# DD2088PoE_Daisy_Chain_IMU.net
KiCad netlist of a schematic drawn in Altium Designer
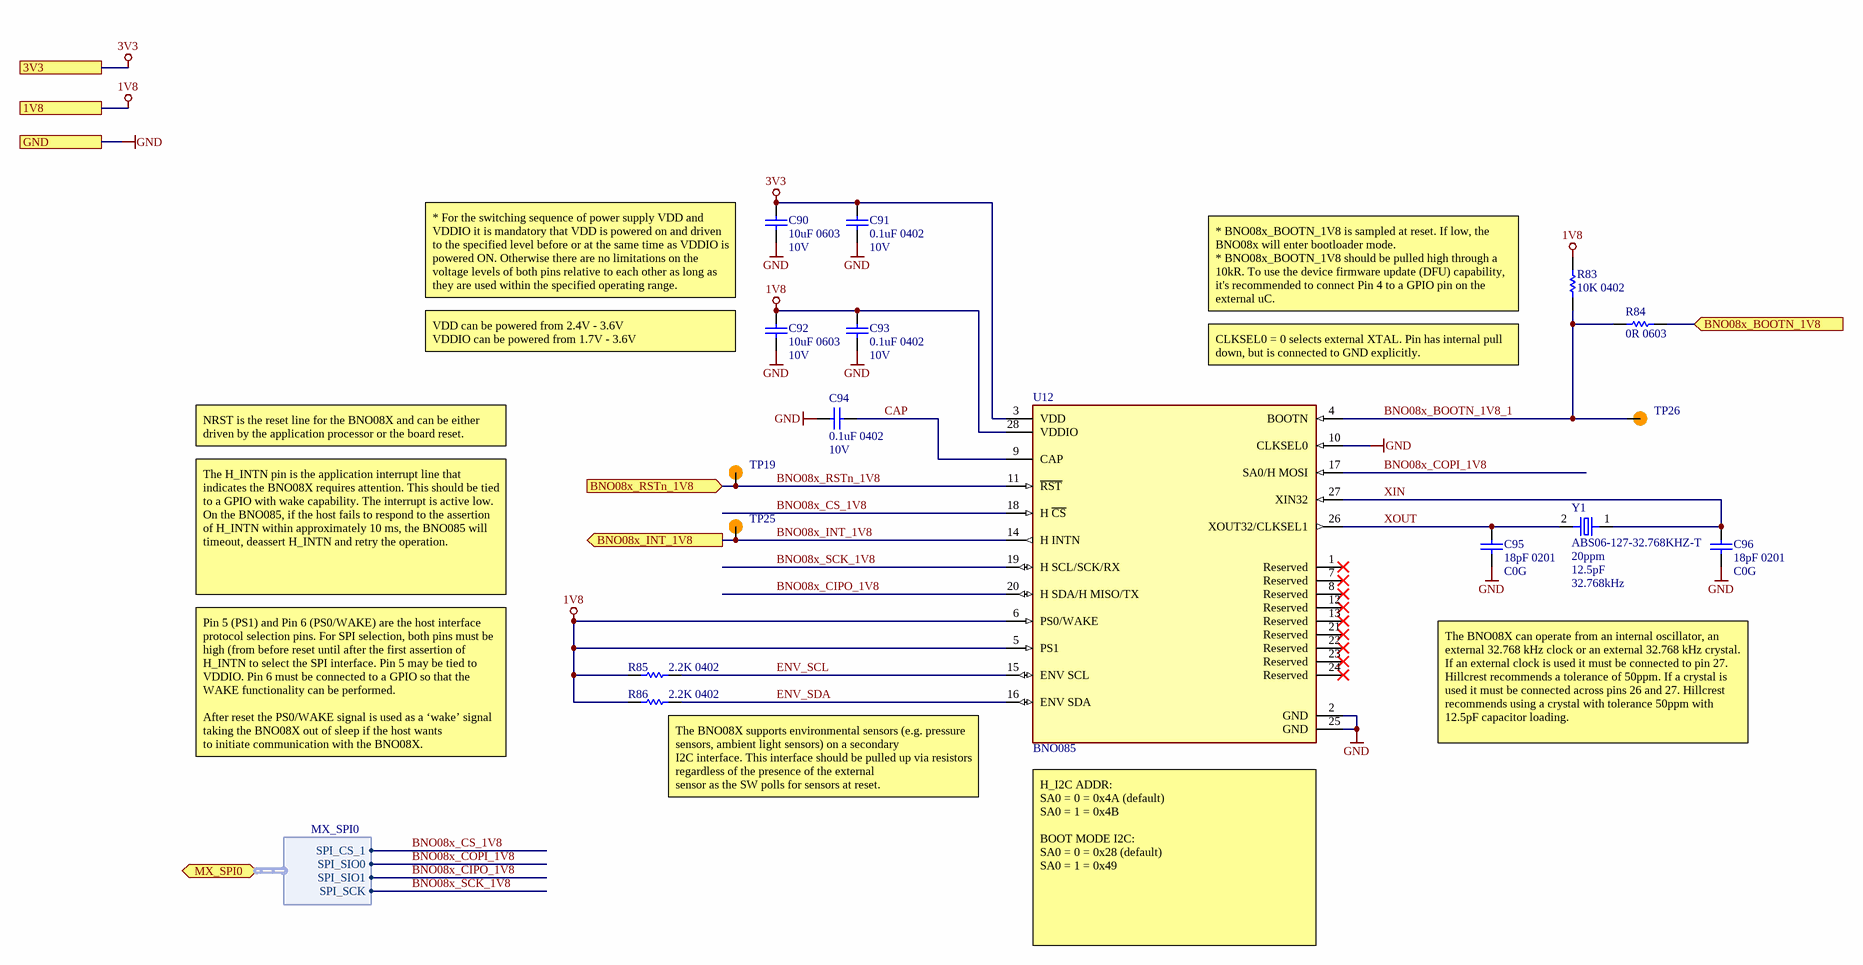
[diagram p0: DD2088PoE_Daisy_Chain_IMU.SchDoc]

(export (version "E")
  (design (tool "Eeschema 10.0.6"))
  (components
    (comp (ref "C90")
      (value "10uF 0603")
      (footprint "CAP_Altium_Vault_Generic:CAPC0603(1608)100_L")
      (description "CAP CER 10UF 10V X5R 0603 20%")
      (fields (field (name "TOLERANCE") "20%") (field (name "VOLTAGE RATING") "10V"))
      (libsource (lib "LuxonisMaster") (part "GRM188R61A106ME69D"))
    )
    (comp (ref "C91")
      (value "0.1uF 0402")
      (footprint "CAP_Altium_Vault_Generic:CAPC0402(1005)70_L")
      (description "CAP CER 0.1UF 10V X7R 0402 5%")
      (fields (field (name "TOLERANCE") "5%") (field (name "VOLTAGE RATING") "10V"))
      (libsource (lib "LuxonisMaster") (part "GRM155R71A104JA01D"))
    )
    (comp (ref "C92")
      (value "10uF 0603")
      (footprint "CAP_Altium_Vault_Generic:CAPC0603(1608)100_L")
      (description "CAP CER 10UF 10V X5R 0603 20%")
      (fields (field (name "TOLERANCE") "20%") (field (name "VOLTAGE RATING") "10V"))
      (libsource (lib "LuxonisMaster") (part "GRM188R61A106ME69D"))
    )
    (comp (ref "C93")
      (value "0.1uF 0402")
      (footprint "CAP_Altium_Vault_Generic:CAPC0402(1005)70_L")
      (description "CAP CER 0.1UF 10V X7R 0402 5%")
      (fields (field (name "TOLERANCE") "5%") (field (name "VOLTAGE RATING") "10V"))
      (libsource (lib "LuxonisMaster") (part "GRM155R71A104JA01D"))
    )
    (comp (ref "C94")
      (value "0.1uF 0402")
      (footprint "CAP_Altium_Vault_Generic:CAPC0402(1005)70_L")
      (description "CAP CER 0.1UF 10V X7R 0402 5%")
      (fields (field (name "TOLERANCE") "5%") (field (name "VOLTAGE RATING") "10V"))
      (libsource (lib "LuxonisMaster") (part "GRM155R71A104JA01D"))
    )
    (comp (ref "C95")
      (value "18pF 0201")
      (footprint "CAP_Altium_Vault_Generic:CAPC0201(0603)33_L")
      (description "Cap Ceramic 18pF 25V C0G 1% Pad SMD 0201 125C T/R")
      (fields (field (name "TOLERANCE") "1%") (field (name "DIELECTRIC") "C0G"))
      (libsource (lib "BW1092_R0M0E0") (part "GRM0335C1E180FA01D"))
    )
    (comp (ref "C96")
      (value "18pF 0201")
      (footprint "CAP_Altium_Vault_Generic:CAPC0201(0603)33_L")
      (description "Cap Ceramic 18pF 25V C0G 1% Pad SMD 0201 125C T/R")
      (fields (field (name "TOLERANCE") "1%") (field (name "DIELECTRIC") "C0G"))
      (libsource (lib "BW1092_R0M0E0") (part "GRM0335C1E180FA01D"))
    )
    (comp (ref "R83")
      (value "10K 0402")
      (footprint "RES_Altium_Vault_Generic:RESC0402(1005)_L")
      (fields (field (name "TOLERANCE") "1%"))
      (libsource (lib "LuxonisMaster") (part "RC0402FR-1310KL"))
    )
    (comp (ref "R84")
      (value "0R 0603")
      (footprint "RES_Altium_Vault_Generic:RESC0603(1608)_L")
      (fields (field (name "TOLERANCE") "5%"))
      (libsource (lib "LuxonisMaster") (part "CRCW06030000Z0EA"))
    )
    (comp (ref "R85")
      (value "2.2K 0402")
      (footprint "RES_Altium_Vault_Generic:RESC0402(1005)_L")
      (description "RES SMD 2.2K OHM 1% 1/16W 0402")
      (fields (field (name "TOLERANCE") "1%"))
      (libsource (lib "LuxonisMaster") (part "RC0402FR-072K2L"))
    )
    (comp (ref "R86")
      (value "2.2K 0402")
      (footprint "RES_Altium_Vault_Generic:RESC0402(1005)_L")
      (description "RES SMD 2.2K OHM 1% 1/16W 0402")
      (fields (field (name "TOLERANCE") "1%"))
      (libsource (lib "LuxonisMaster") (part "RC0402FR-072K2L"))
    )
    (comp (ref "TP19")
      (value "TP100_200_NS")
      (footprint "TP100_200_NS")
      (libsource (lib "LuxonisMaster") (part "TEST_POINT"))
    )
    (comp (ref "TP25")
      (value "TP100_200_NS")
      (footprint "TP100_200_NS")
      (libsource (lib "LuxonisMaster") (part "TEST_POINT"))
    )
    (comp (ref "TP26")
      (value "TP100_200_NS")
      (footprint "TP100_200_NS")
      (libsource (lib "LuxonisMaster") (part "TEST_POINT"))
    )
    (comp (ref "U12")
      (value "BNO085")
      (footprint "BW1092_R0M0E0:BNO085")
      (description "IMU ACCEL/GYRO/MAG I2C 32BIT")
      (libsource (lib "BW1092_R0M0E0") (part "BNO085"))
    )
    (comp (ref "Y1")
      (value "ABS06-127-32.768KHZ-T")
      (footprint "BW1092_R0M0E0:ABS06-127-32.768KHZ-T")
      (description "CRYSTAL 32.768kHz ±20ppm Crystal 12.5pF 90 kOhms 2-SMD, No Lead")
      (fields
        (field (name "FREQUENCY TOLERANCE") "20ppm")
        (field (name "LOAD CAPACITANCE") "12.5pF")
        (field (name "FREQUENCY") "32.768kHz")
      )
      (libsource (lib "BW1092_R0M0E0") (part "ABS06-127-32.768KHZ-T"))
    )
  )
  (nets
    (net (code "2") (name "/BNO08x_BOOTN_1V8") (class "Default")
      (node (ref "R84") (pin "2") (pinfunction "2_2") (pintype "passive"))
    )
    (net (code "3") (name "/BNO08x_BOOTN_1V8_1") (class "Default")
      (node (ref "R83") (pin "1") (pinfunction "1_1") (pintype "passive"))
      (node (ref "R84") (pin "1") (pinfunction "1_1") (pintype "passive"))
      (node (ref "TP26") (pin "1") (pintype "passive"))
      (node (ref "U12") (pin "4") (pinfunction "BOOTN_4") (pintype "input"))
    )
    (net (code "4") (name "/BNO08x_CIPO_1V8") (class "Default")
      (node (ref "U12") (pin "20") (pinfunction "H_SDA/H_MISO/TX_20") (pintype "bidirectional"))
    )
    (net (code "5") (name "/BNO08x_COPI_1V8") (class "Default")
      (node (ref "U12") (pin "17") (pinfunction "SA0/H_MOSI_17") (pintype "input"))
    )
    (net (code "6") (name "/BNO08x_CS_1V8") (class "Default")
      (node (ref "U12") (pin "18") (pinfunction "H_~{CS}_18") (pintype "input"))
    )
    (net (code "7") (name "/BNO08x_INT_1V8") (class "Default")
      (node (ref "TP25") (pin "1") (pintype "passive"))
      (node (ref "U12") (pin "14") (pinfunction "H_INTN_14") (pintype "output"))
    )
    (net (code "8") (name "/BNO08x_RSTn_1V8") (class "Default")
      (node (ref "TP19") (pin "1") (pintype "passive"))
      (node (ref "U12") (pin "11") (pinfunction "~{RST}_11") (pintype "input"))
    )
    (net (code "9") (name "/BNO08x_SCK_1V8") (class "Default")
      (node (ref "U12") (pin "19") (pinfunction "H_SCL/SCK/RX_19") (pintype "bidirectional"))
    )
    (net (code "10") (name "/CAP") (class "Default")
      (node (ref "C94") (pin "1") (pinfunction "1_1") (pintype "passive"))
      (node (ref "U12") (pin "9") (pinfunction "CAP_9") (pintype "passive"))
    )
    (net (code "11") (name "/ENV_SCL") (class "Default")
      (node (ref "R85") (pin "2") (pinfunction "2_2") (pintype "passive"))
      (node (ref "U12") (pin "15") (pinfunction "ENV_SCL_15") (pintype "bidirectional"))
    )
    (net (code "12") (name "/ENV_SDA") (class "Default")
      (node (ref "R86") (pin "2") (pinfunction "2_2") (pintype "passive"))
      (node (ref "U12") (pin "16") (pinfunction "ENV_SDA_16") (pintype "bidirectional"))
    )
    (net (code "13") (name "/XIN") (class "Default")
      (node (ref "C96") (pin "2") (pinfunction "2_2") (pintype "passive"))
      (node (ref "U12") (pin "27") (pinfunction "XIN32_27") (pintype "input"))
      (node (ref "Y1") (pin "1") (pinfunction "1_1") (pintype "passive"))
    )
    (net (code "14") (name "/XOUT") (class "Default")
      (node (ref "C95") (pin "2") (pinfunction "2_2") (pintype "passive"))
      (node (ref "U12") (pin "26") (pinfunction "XOUT32/CLKSEL1_26") (pintype "output"))
      (node (ref "Y1") (pin "2") (pinfunction "2_2") (pintype "passive"))
    )
    (net (code "16") (name "1V8") (class "Default")
      (node (ref "C92") (pin "2") (pinfunction "2_2") (pintype "passive"))
      (node (ref "C93") (pin "2") (pinfunction "2_2") (pintype "passive"))
      (node (ref "R83") (pin "2") (pinfunction "2_2") (pintype "passive"))
      (node (ref "R85") (pin "1") (pinfunction "1_1") (pintype "passive"))
      (node (ref "R86") (pin "1") (pinfunction "1_1") (pintype "passive"))
      (node (ref "U12") (pin "28") (pinfunction "VDDIO_28") (pintype "power_in"))
      (node (ref "U12") (pin "5") (pinfunction "PS1_5") (pintype "input"))
      (node (ref "U12") (pin "6") (pinfunction "PS0/WAKE_6") (pintype "input"))
    )
    (net (code "17") (name "3V3") (class "Default")
      (node (ref "C90") (pin "2") (pinfunction "2_2") (pintype "passive"))
      (node (ref "C91") (pin "2") (pinfunction "2_2") (pintype "passive"))
      (node (ref "U12") (pin "3") (pinfunction "VDD_3") (pintype "power_in"))
    )
    (net (code "18") (name "GND") (class "Default")
      (node (ref "C90") (pin "1") (pinfunction "1_1") (pintype "passive"))
      (node (ref "C91") (pin "1") (pinfunction "1_1") (pintype "passive"))
      (node (ref "C92") (pin "1") (pinfunction "1_1") (pintype "passive"))
      (node (ref "C93") (pin "1") (pinfunction "1_1") (pintype "passive"))
      (node (ref "C94") (pin "2") (pinfunction "2_2") (pintype "passive"))
      (node (ref "C95") (pin "1") (pinfunction "1_1") (pintype "passive"))
      (node (ref "C96") (pin "1") (pinfunction "1_1") (pintype "passive"))
      (node (ref "U12") (pin "10") (pinfunction "CLKSEL0_10") (pintype "input"))
      (node (ref "U12") (pin "2") (pinfunction "GND_2") (pintype "power_in"))
      (node (ref "U12") (pin "25") (pinfunction "GND_25") (pintype "power_in"))
    )
    (net (code "19") (name "unconnected-(U12-Reserved-Pad1)") (class "Default")
      (node (ref "U12") (pin "1") (pinfunction "Reserved_1") (pintype "passive+no_connect"))
    )
    (net (code "20") (name "unconnected-(U12-Reserved-Pad7)") (class "Default")
      (node (ref "U12") (pin "7") (pinfunction "Reserved_7") (pintype "passive+no_connect"))
    )
    (net (code "21") (name "unconnected-(U12-Reserved-Pad8)") (class "Default")
      (node (ref "U12") (pin "8") (pinfunction "Reserved_8") (pintype "passive+no_connect"))
    )
    (net (code "22") (name "unconnected-(U12-Reserved-Pad12)") (class "Default")
      (node (ref "U12") (pin "12") (pinfunction "Reserved_12") (pintype "passive+no_connect"))
    )
    (net (code "23") (name "unconnected-(U12-Reserved-Pad13)") (class "Default")
      (node (ref "U12") (pin "13") (pinfunction "Reserved_13") (pintype "passive+no_connect"))
    )
    (net (code "24") (name "unconnected-(U12-Reserved-Pad21)") (class "Default")
      (node (ref "U12") (pin "21") (pinfunction "Reserved_21") (pintype "passive+no_connect"))
    )
    (net (code "25") (name "unconnected-(U12-Reserved-Pad22)") (class "Default")
      (node (ref "U12") (pin "22") (pinfunction "Reserved_22") (pintype "passive+no_connect"))
    )
    (net (code "26") (name "unconnected-(U12-Reserved-Pad23)") (class "Default")
      (node (ref "U12") (pin "23") (pinfunction "Reserved_23") (pintype "passive+no_connect"))
    )
    (net (code "27") (name "unconnected-(U12-Reserved-Pad24)") (class "Default")
      (node (ref "U12") (pin "24") (pinfunction "Reserved_24") (pintype "passive+no_connect"))
    )
  )
)
